# M930.net
KiCad netlist of a schematic drawn in EAGLE
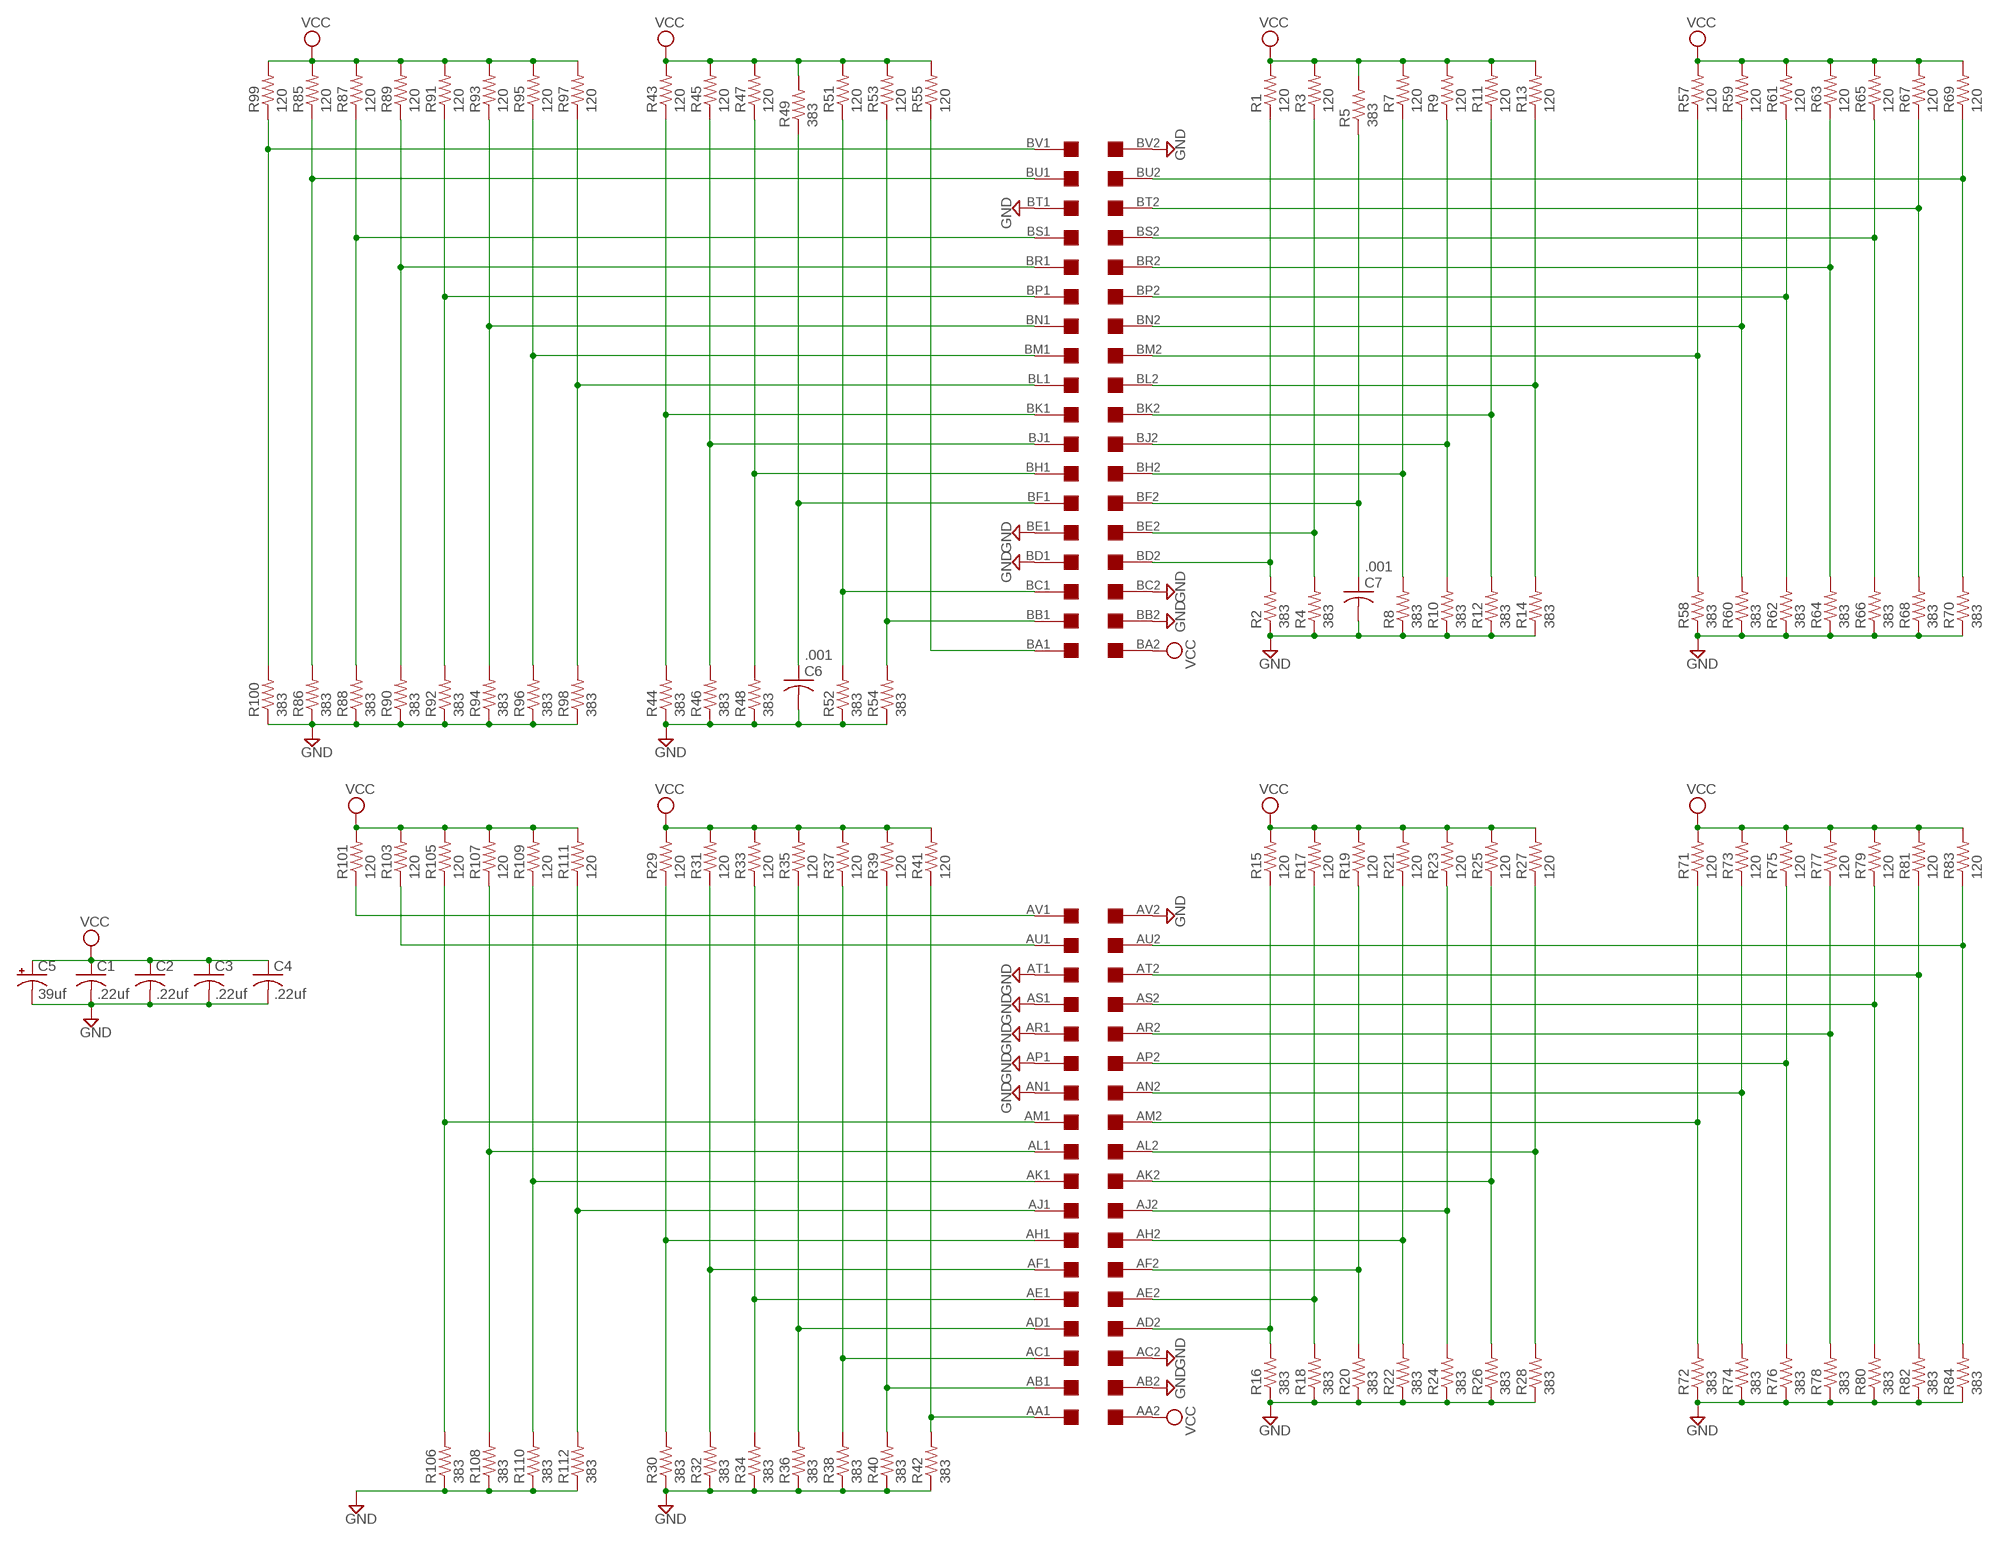
[diagram p0: schematic, sheet 1]

(export (version "E")
  (design (tool "Eeschema 10.0.6"))
  (components
    (comp (ref "C1")
      (value ".22uf")
      (footprint "eagle-import:C050-025X075")
      (libsource (lib "eagle-import") (part "C-US050-025X075"))
    )
    (comp (ref "C2")
      (value ".22uf")
      (footprint "eagle-import:C050-025X075")
      (libsource (lib "eagle-import") (part "C-US050-025X075"))
    )
    (comp (ref "C3")
      (value ".22uf")
      (footprint "eagle-import:C050-025X075")
      (libsource (lib "eagle-import") (part "C-US050-025X075"))
    )
    (comp (ref "C4")
      (value ".22uf")
      (footprint "eagle-import:C050-025X075")
      (libsource (lib "eagle-import") (part "C-US050-025X075"))
    )
    (comp (ref "C5")
      (value "39uf")
      (footprint "eagle-import:E15-5")
      (libsource (lib "eagle-import") (part "CPOL-USE15-5AXIAL"))
    )
    (comp (ref "C6")
      (value ".001")
      (footprint "eagle-import:C050-025X075")
      (libsource (lib "eagle-import") (part "C-US050-025X075"))
    )
    (comp (ref "C7")
      (value ".001")
      (footprint "eagle-import:C050-025X075")
      (libsource (lib "eagle-import") (part "C-US050-025X075"))
    )
    (comp (ref "R1")
      (value "120")
      (footprint "eagle-import:0207_10")
      (libsource (lib "eagle-import") (part "R-US_0207/10"))
    )
    (comp (ref "R2")
      (value "383")
      (footprint "eagle-import:0207_10")
      (libsource (lib "eagle-import") (part "R-US_0207/10"))
    )
    (comp (ref "R3")
      (value "120")
      (footprint "eagle-import:0207_10")
      (libsource (lib "eagle-import") (part "R-US_0207/10"))
    )
    (comp (ref "R4")
      (value "383")
      (footprint "eagle-import:0207_10")
      (libsource (lib "eagle-import") (part "R-US_0207/10"))
    )
    (comp (ref "R5")
      (value "383")
      (footprint "eagle-import:0207_10")
      (libsource (lib "eagle-import") (part "R-US_0207/10"))
    )
    (comp (ref "R7")
      (value "120")
      (footprint "eagle-import:0207_10")
      (libsource (lib "eagle-import") (part "R-US_0207/10"))
    )
    (comp (ref "R8")
      (value "383")
      (footprint "eagle-import:0207_10")
      (libsource (lib "eagle-import") (part "R-US_0207/10"))
    )
    (comp (ref "R9")
      (value "120")
      (footprint "eagle-import:0207_10")
      (libsource (lib "eagle-import") (part "R-US_0207/10"))
    )
    (comp (ref "R10")
      (value "383")
      (footprint "eagle-import:0207_10")
      (libsource (lib "eagle-import") (part "R-US_0207/10"))
    )
    (comp (ref "R11")
      (value "120")
      (footprint "eagle-import:0207_10")
      (libsource (lib "eagle-import") (part "R-US_0207/10"))
    )
    (comp (ref "R12")
      (value "383")
      (footprint "eagle-import:0207_10")
      (libsource (lib "eagle-import") (part "R-US_0207/10"))
    )
    (comp (ref "R13")
      (value "120")
      (footprint "eagle-import:0207_10")
      (libsource (lib "eagle-import") (part "R-US_0207/10"))
    )
    (comp (ref "R14")
      (value "383")
      (footprint "eagle-import:0207_10")
      (libsource (lib "eagle-import") (part "R-US_0207/10"))
    )
    (comp (ref "R15")
      (value "120")
      (footprint "eagle-import:0207_10")
      (libsource (lib "eagle-import") (part "R-US_0207/10"))
    )
    (comp (ref "R16")
      (value "383")
      (footprint "eagle-import:0207_10")
      (libsource (lib "eagle-import") (part "R-US_0207/10"))
    )
    (comp (ref "R17")
      (value "120")
      (footprint "eagle-import:0207_10")
      (libsource (lib "eagle-import") (part "R-US_0207/10"))
    )
    (comp (ref "R18")
      (value "383")
      (footprint "eagle-import:0207_10")
      (libsource (lib "eagle-import") (part "R-US_0207/10"))
    )
    (comp (ref "R19")
      (value "120")
      (footprint "eagle-import:0207_10")
      (libsource (lib "eagle-import") (part "R-US_0207/10"))
    )
    (comp (ref "R20")
      (value "383")
      (footprint "eagle-import:0207_10")
      (libsource (lib "eagle-import") (part "R-US_0207/10"))
    )
    (comp (ref "R21")
      (value "120")
      (footprint "eagle-import:0207_10")
      (libsource (lib "eagle-import") (part "R-US_0207/10"))
    )
    (comp (ref "R22")
      (value "383")
      (footprint "eagle-import:0207_10")
      (libsource (lib "eagle-import") (part "R-US_0207/10"))
    )
    (comp (ref "R23")
      (value "120")
      (footprint "eagle-import:0207_10")
      (libsource (lib "eagle-import") (part "R-US_0207/10"))
    )
    (comp (ref "R24")
      (value "383")
      (footprint "eagle-import:0207_10")
      (libsource (lib "eagle-import") (part "R-US_0207/10"))
    )
    (comp (ref "R25")
      (value "120")
      (footprint "eagle-import:0207_10")
      (libsource (lib "eagle-import") (part "R-US_0207/10"))
    )
    (comp (ref "R26")
      (value "383")
      (footprint "eagle-import:0207_10")
      (libsource (lib "eagle-import") (part "R-US_0207/10"))
    )
    (comp (ref "R27")
      (value "120")
      (footprint "eagle-import:0207_10")
      (libsource (lib "eagle-import") (part "R-US_0207/10"))
    )
    (comp (ref "R28")
      (value "383")
      (footprint "eagle-import:0207_10")
      (libsource (lib "eagle-import") (part "R-US_0207/10"))
    )
    (comp (ref "R29")
      (value "120")
      (footprint "eagle-import:0207_10")
      (libsource (lib "eagle-import") (part "R-US_0207/10"))
    )
    (comp (ref "R30")
      (value "383")
      (footprint "eagle-import:0207_10")
      (libsource (lib "eagle-import") (part "R-US_0207/10"))
    )
    (comp (ref "R31")
      (value "120")
      (footprint "eagle-import:0207_10")
      (libsource (lib "eagle-import") (part "R-US_0207/10"))
    )
    (comp (ref "R32")
      (value "383")
      (footprint "eagle-import:0207_10")
      (libsource (lib "eagle-import") (part "R-US_0207/10"))
    )
    (comp (ref "R33")
      (value "120")
      (footprint "eagle-import:0207_10")
      (libsource (lib "eagle-import") (part "R-US_0207/10"))
    )
    (comp (ref "R34")
      (value "383")
      (footprint "eagle-import:0207_10")
      (libsource (lib "eagle-import") (part "R-US_0207/10"))
    )
    (comp (ref "R35")
      (value "120")
      (footprint "eagle-import:0207_10")
      (libsource (lib "eagle-import") (part "R-US_0207/10"))
    )
    (comp (ref "R36")
      (value "383")
      (footprint "eagle-import:0207_10")
      (libsource (lib "eagle-import") (part "R-US_0207/10"))
    )
    (comp (ref "R37")
      (value "120")
      (footprint "eagle-import:0207_10")
      (libsource (lib "eagle-import") (part "R-US_0207/10"))
    )
    (comp (ref "R38")
      (value "383")
      (footprint "eagle-import:0207_10")
      (libsource (lib "eagle-import") (part "R-US_0207/10"))
    )
    (comp (ref "R39")
      (value "120")
      (footprint "eagle-import:0207_10")
      (libsource (lib "eagle-import") (part "R-US_0207/10"))
    )
    (comp (ref "R40")
      (value "383")
      (footprint "eagle-import:0207_10")
      (libsource (lib "eagle-import") (part "R-US_0207/10"))
    )
    (comp (ref "R41")
      (value "120")
      (footprint "eagle-import:0207_10")
      (libsource (lib "eagle-import") (part "R-US_0207/10"))
    )
    (comp (ref "R42")
      (value "383")
      (footprint "eagle-import:0207_10")
      (libsource (lib "eagle-import") (part "R-US_0207/10"))
    )
    (comp (ref "R43")
      (value "120")
      (footprint "eagle-import:0207_10")
      (libsource (lib "eagle-import") (part "R-US_0207/10"))
    )
    (comp (ref "R44")
      (value "383")
      (footprint "eagle-import:0207_10")
      (libsource (lib "eagle-import") (part "R-US_0207/10"))
    )
    (comp (ref "R45")
      (value "120")
      (footprint "eagle-import:0207_10")
      (libsource (lib "eagle-import") (part "R-US_0207/10"))
    )
    (comp (ref "R46")
      (value "383")
      (footprint "eagle-import:0207_10")
      (libsource (lib "eagle-import") (part "R-US_0207/10"))
    )
    (comp (ref "R47")
      (value "120")
      (footprint "eagle-import:0207_10")
      (libsource (lib "eagle-import") (part "R-US_0207/10"))
    )
    (comp (ref "R48")
      (value "383")
      (footprint "eagle-import:0207_10")
      (libsource (lib "eagle-import") (part "R-US_0207/10"))
    )
    (comp (ref "R49")
      (value "383")
      (footprint "eagle-import:0207_10")
      (libsource (lib "eagle-import") (part "R-US_0207/10"))
    )
    (comp (ref "R51")
      (value "120")
      (footprint "eagle-import:0207_10")
      (libsource (lib "eagle-import") (part "R-US_0207/10"))
    )
    (comp (ref "R52")
      (value "383")
      (footprint "eagle-import:0207_10")
      (libsource (lib "eagle-import") (part "R-US_0207/10"))
    )
    (comp (ref "R53")
      (value "120")
      (footprint "eagle-import:0207_10")
      (libsource (lib "eagle-import") (part "R-US_0207/10"))
    )
    (comp (ref "R54")
      (value "383")
      (footprint "eagle-import:0207_10")
      (libsource (lib "eagle-import") (part "R-US_0207/10"))
    )
    (comp (ref "R55")
      (value "120")
      (footprint "eagle-import:0207_10")
      (libsource (lib "eagle-import") (part "R-US_0207/10"))
    )
    (comp (ref "R57")
      (value "120")
      (footprint "eagle-import:0207_10")
      (libsource (lib "eagle-import") (part "R-US_0207/10"))
    )
    (comp (ref "R58")
      (value "383")
      (footprint "eagle-import:0207_10")
      (libsource (lib "eagle-import") (part "R-US_0207/10"))
    )
    (comp (ref "R59")
      (value "120")
      (footprint "eagle-import:0207_10")
      (libsource (lib "eagle-import") (part "R-US_0207/10"))
    )
    (comp (ref "R60")
      (value "383")
      (footprint "eagle-import:0207_10")
      (libsource (lib "eagle-import") (part "R-US_0207/10"))
    )
    (comp (ref "R61")
      (value "120")
      (footprint "eagle-import:0207_10")
      (libsource (lib "eagle-import") (part "R-US_0207/10"))
    )
    (comp (ref "R62")
      (value "383")
      (footprint "eagle-import:0207_10")
      (libsource (lib "eagle-import") (part "R-US_0207/10"))
    )
    (comp (ref "R63")
      (value "120")
      (footprint "eagle-import:0207_10")
      (libsource (lib "eagle-import") (part "R-US_0207/10"))
    )
    (comp (ref "R64")
      (value "383")
      (footprint "eagle-import:0207_10")
      (libsource (lib "eagle-import") (part "R-US_0207/10"))
    )
    (comp (ref "R65")
      (value "120")
      (footprint "eagle-import:0207_10")
      (libsource (lib "eagle-import") (part "R-US_0207/10"))
    )
    (comp (ref "R66")
      (value "383")
      (footprint "eagle-import:0207_10")
      (libsource (lib "eagle-import") (part "R-US_0207/10"))
    )
    (comp (ref "R67")
      (value "120")
      (footprint "eagle-import:0207_10")
      (libsource (lib "eagle-import") (part "R-US_0207/10"))
    )
    (comp (ref "R68")
      (value "383")
      (footprint "eagle-import:0207_10")
      (libsource (lib "eagle-import") (part "R-US_0207/10"))
    )
    (comp (ref "R69")
      (value "120")
      (footprint "eagle-import:0207_10")
      (libsource (lib "eagle-import") (part "R-US_0207/10"))
    )
    (comp (ref "R70")
      (value "383")
      (footprint "eagle-import:0207_10")
      (libsource (lib "eagle-import") (part "R-US_0207/10"))
    )
    (comp (ref "R71")
      (value "120")
      (footprint "eagle-import:0207_10")
      (libsource (lib "eagle-import") (part "R-US_0207/10"))
    )
    (comp (ref "R72")
      (value "383")
      (footprint "eagle-import:0207_10")
      (libsource (lib "eagle-import") (part "R-US_0207/10"))
    )
    (comp (ref "R73")
      (value "120")
      (footprint "eagle-import:0207_10")
      (libsource (lib "eagle-import") (part "R-US_0207/10"))
    )
    (comp (ref "R74")
      (value "383")
      (footprint "eagle-import:0207_10")
      (libsource (lib "eagle-import") (part "R-US_0207/10"))
    )
    (comp (ref "R75")
      (value "120")
      (footprint "eagle-import:0207_10")
      (libsource (lib "eagle-import") (part "R-US_0207/10"))
    )
    (comp (ref "R76")
      (value "383")
      (footprint "eagle-import:0207_10")
      (libsource (lib "eagle-import") (part "R-US_0207/10"))
    )
    (comp (ref "R77")
      (value "120")
      (footprint "eagle-import:0207_10")
      (libsource (lib "eagle-import") (part "R-US_0207/10"))
    )
    (comp (ref "R78")
      (value "383")
      (footprint "eagle-import:0207_10")
      (libsource (lib "eagle-import") (part "R-US_0207/10"))
    )
    (comp (ref "R79")
      (value "120")
      (footprint "eagle-import:0207_10")
      (libsource (lib "eagle-import") (part "R-US_0207/10"))
    )
    (comp (ref "R80")
      (value "383")
      (footprint "eagle-import:0207_10")
      (libsource (lib "eagle-import") (part "R-US_0207/10"))
    )
    (comp (ref "R81")
      (value "120")
      (footprint "eagle-import:0207_10")
      (libsource (lib "eagle-import") (part "R-US_0207/10"))
    )
    (comp (ref "R82")
      (value "383")
      (footprint "eagle-import:0207_10")
      (libsource (lib "eagle-import") (part "R-US_0207/10"))
    )
    (comp (ref "R83")
      (value "120")
      (footprint "eagle-import:0207_10")
      (libsource (lib "eagle-import") (part "R-US_0207/10"))
    )
    (comp (ref "R84")
      (value "383")
      (footprint "eagle-import:0207_10")
      (libsource (lib "eagle-import") (part "R-US_0207/10"))
    )
    (comp (ref "R85")
      (value "120")
      (footprint "eagle-import:0207_10")
      (libsource (lib "eagle-import") (part "R-US_0207/10"))
    )
    (comp (ref "R86")
      (value "383")
      (footprint "eagle-import:0207_10")
      (libsource (lib "eagle-import") (part "R-US_0207/10"))
    )
    (comp (ref "R87")
      (value "120")
      (footprint "eagle-import:0207_10")
      (libsource (lib "eagle-import") (part "R-US_0207/10"))
    )
    (comp (ref "R88")
      (value "383")
      (footprint "eagle-import:0207_10")
      (libsource (lib "eagle-import") (part "R-US_0207/10"))
    )
    (comp (ref "R89")
      (value "120")
      (footprint "eagle-import:0207_10")
      (libsource (lib "eagle-import") (part "R-US_0207/10"))
    )
    (comp (ref "R90")
      (value "383")
      (footprint "eagle-import:0207_10")
      (libsource (lib "eagle-import") (part "R-US_0207/10"))
    )
    (comp (ref "R91")
      (value "120")
      (footprint "eagle-import:0207_10")
      (libsource (lib "eagle-import") (part "R-US_0207/10"))
    )
    (comp (ref "R92")
      (value "383")
      (footprint "eagle-import:0207_10")
      (libsource (lib "eagle-import") (part "R-US_0207/10"))
    )
    (comp (ref "R93")
      (value "120")
      (footprint "eagle-import:0207_10")
      (libsource (lib "eagle-import") (part "R-US_0207/10"))
    )
    (comp (ref "R94")
      (value "383")
      (footprint "eagle-import:0207_10")
      (libsource (lib "eagle-import") (part "R-US_0207/10"))
    )
    (comp (ref "R95")
      (value "120")
      (footprint "eagle-import:0207_10")
      (libsource (lib "eagle-import") (part "R-US_0207/10"))
    )
    (comp (ref "R96")
      (value "383")
      (footprint "eagle-import:0207_10")
      (libsource (lib "eagle-import") (part "R-US_0207/10"))
    )
    (comp (ref "R97")
      (value "120")
      (footprint "eagle-import:0207_10")
      (libsource (lib "eagle-import") (part "R-US_0207/10"))
    )
    (comp (ref "R98")
      (value "383")
      (footprint "eagle-import:0207_10")
      (libsource (lib "eagle-import") (part "R-US_0207/10"))
    )
    (comp (ref "R99")
      (value "120")
      (footprint "eagle-import:0207_10")
      (libsource (lib "eagle-import") (part "R-US_0207/10"))
    )
    (comp (ref "R100")
      (value "383")
      (footprint "eagle-import:0207_10")
      (libsource (lib "eagle-import") (part "R-US_0207/10"))
    )
    (comp (ref "R101")
      (value "120")
      (footprint "eagle-import:0207_10")
      (libsource (lib "eagle-import") (part "R-US_0207/10"))
    )
    (comp (ref "R103")
      (value "120")
      (footprint "eagle-import:0207_10")
      (libsource (lib "eagle-import") (part "R-US_0207/10"))
    )
    (comp (ref "R105")
      (value "120")
      (footprint "eagle-import:0207_10")
      (libsource (lib "eagle-import") (part "R-US_0207/10"))
    )
    (comp (ref "R106")
      (value "383")
      (footprint "eagle-import:0207_10")
      (libsource (lib "eagle-import") (part "R-US_0207/10"))
    )
    (comp (ref "R107")
      (value "120")
      (footprint "eagle-import:0207_10")
      (libsource (lib "eagle-import") (part "R-US_0207/10"))
    )
    (comp (ref "R108")
      (value "383")
      (footprint "eagle-import:0207_10")
      (libsource (lib "eagle-import") (part "R-US_0207/10"))
    )
    (comp (ref "R109")
      (value "120")
      (footprint "eagle-import:0207_10")
      (libsource (lib "eagle-import") (part "R-US_0207/10"))
    )
    (comp (ref "R110")
      (value "383")
      (footprint "eagle-import:0207_10")
      (libsource (lib "eagle-import") (part "R-US_0207/10"))
    )
    (comp (ref "R111")
      (value "120")
      (footprint "eagle-import:0207_10")
      (libsource (lib "eagle-import") (part "R-US_0207/10"))
    )
    (comp (ref "R112")
      (value "383")
      (footprint "eagle-import:0207_10")
      (libsource (lib "eagle-import") (part "R-US_0207/10"))
    )
    (comp (ref "U$1")
      (value "DOUBLE")
      (footprint "eagle-import:EDGE-CON4")
      (libsource (lib "eagle-import") (part "DOUBLE"))
    )
  )
  (nets
    (net (code "1") (name "GND") (class "Default")
      (node (ref "C1") (pin "2") (pinfunction "2_2") (pintype "passive"))
      (node (ref "C2") (pin "2") (pinfunction "2_2") (pintype "passive"))
      (node (ref "C3") (pin "2") (pinfunction "2_2") (pintype "passive"))
      (node (ref "C4") (pin "2") (pinfunction "2_2") (pintype "passive"))
      (node (ref "C5") (pin "-") (pinfunction "-_-") (pintype "passive"))
      (node (ref "C6") (pin "2") (pinfunction "2_2") (pintype "passive"))
      (node (ref "C7") (pin "2") (pinfunction "2_2") (pintype "passive"))
      (node (ref "R10") (pin "1") (pinfunction "1_1") (pintype "passive"))
      (node (ref "R100") (pin "1") (pinfunction "1_1") (pintype "passive"))
      (node (ref "R106") (pin "1") (pinfunction "1_1") (pintype "passive"))
      (node (ref "R108") (pin "1") (pinfunction "1_1") (pintype "passive"))
      (node (ref "R110") (pin "1") (pinfunction "1_1") (pintype "passive"))
      (node (ref "R112") (pin "1") (pinfunction "1_1") (pintype "passive"))
      (node (ref "R12") (pin "1") (pinfunction "1_1") (pintype "passive"))
      (node (ref "R14") (pin "1") (pinfunction "1_1") (pintype "passive"))
      (node (ref "R16") (pin "1") (pinfunction "1_1") (pintype "passive"))
      (node (ref "R18") (pin "1") (pinfunction "1_1") (pintype "passive"))
      (node (ref "R2") (pin "1") (pinfunction "1_1") (pintype "passive"))
      (node (ref "R20") (pin "1") (pinfunction "1_1") (pintype "passive"))
      (node (ref "R22") (pin "1") (pinfunction "1_1") (pintype "passive"))
      (node (ref "R24") (pin "1") (pinfunction "1_1") (pintype "passive"))
      (node (ref "R26") (pin "1") (pinfunction "1_1") (pintype "passive"))
      (node (ref "R28") (pin "1") (pinfunction "1_1") (pintype "passive"))
      (node (ref "R30") (pin "1") (pinfunction "1_1") (pintype "passive"))
      (node (ref "R32") (pin "1") (pinfunction "1_1") (pintype "passive"))
      (node (ref "R34") (pin "1") (pinfunction "1_1") (pintype "passive"))
      (node (ref "R36") (pin "1") (pinfunction "1_1") (pintype "passive"))
      (node (ref "R38") (pin "1") (pinfunction "1_1") (pintype "passive"))
      (node (ref "R4") (pin "1") (pinfunction "1_1") (pintype "passive"))
      (node (ref "R40") (pin "1") (pinfunction "1_1") (pintype "passive"))
      (node (ref "R42") (pin "1") (pinfunction "1_1") (pintype "passive"))
      (node (ref "R44") (pin "1") (pinfunction "1_1") (pintype "passive"))
      (node (ref "R46") (pin "1") (pinfunction "1_1") (pintype "passive"))
      (node (ref "R48") (pin "1") (pinfunction "1_1") (pintype "passive"))
      (node (ref "R52") (pin "1") (pinfunction "1_1") (pintype "passive"))
      (node (ref "R54") (pin "1") (pinfunction "1_1") (pintype "passive"))
      (node (ref "R58") (pin "1") (pinfunction "1_1") (pintype "passive"))
      (node (ref "R60") (pin "1") (pinfunction "1_1") (pintype "passive"))
      (node (ref "R62") (pin "1") (pinfunction "1_1") (pintype "passive"))
      (node (ref "R64") (pin "1") (pinfunction "1_1") (pintype "passive"))
      (node (ref "R66") (pin "1") (pinfunction "1_1") (pintype "passive"))
      (node (ref "R68") (pin "1") (pinfunction "1_1") (pintype "passive"))
      (node (ref "R70") (pin "1") (pinfunction "1_1") (pintype "passive"))
      (node (ref "R72") (pin "1") (pinfunction "1_1") (pintype "passive"))
      (node (ref "R74") (pin "1") (pinfunction "1_1") (pintype "passive"))
      (node (ref "R76") (pin "1") (pinfunction "1_1") (pintype "passive"))
      (node (ref "R78") (pin "1") (pinfunction "1_1") (pintype "passive"))
      (node (ref "R8") (pin "1") (pinfunction "1_1") (pintype "passive"))
      (node (ref "R80") (pin "1") (pinfunction "1_1") (pintype "passive"))
      (node (ref "R82") (pin "1") (pinfunction "1_1") (pintype "passive"))
      (node (ref "R84") (pin "1") (pinfunction "1_1") (pintype "passive"))
      (node (ref "R86") (pin "1") (pinfunction "1_1") (pintype "passive"))
      (node (ref "R88") (pin "1") (pinfunction "1_1") (pintype "passive"))
      (node (ref "R90") (pin "1") (pinfunction "1_1") (pintype "passive"))
      (node (ref "R92") (pin "1") (pinfunction "1_1") (pintype "passive"))
      (node (ref "R94") (pin "1") (pinfunction "1_1") (pintype "passive"))
      (node (ref "R96") (pin "1") (pinfunction "1_1") (pintype "passive"))
      (node (ref "R98") (pin "1") (pinfunction "1_1") (pintype "passive"))
      (node (ref "U$1") (pin "AB2") (pinfunction "1_AB2") (pintype "bidirectional"))
      (node (ref "U$1") (pin "AC2") (pinfunction "1_AC2") (pintype "bidirectional"))
      (node (ref "U$1") (pin "AN1") (pinfunction "1_AN1") (pintype "bidirectional"))
      (node (ref "U$1") (pin "AP1") (pinfunction "1_AP1") (pintype "bidirectional"))
      (node (ref "U$1") (pin "AR1") (pinfunction "1_AR1") (pintype "bidirectional"))
      (node (ref "U$1") (pin "AS1") (pinfunction "1_AS1") (pintype "bidirectional"))
      (node (ref "U$1") (pin "AT1") (pinfunction "1_AT1") (pintype "bidirectional"))
      (node (ref "U$1") (pin "AV2") (pinfunction "1_AV2") (pintype "bidirectional"))
      (node (ref "U$1") (pin "BB2") (pinfunction "1_BB2") (pintype "bidirectional"))
      (node (ref "U$1") (pin "BC2") (pinfunction "1_BC2") (pintype "bidirectional"))
      (node (ref "U$1") (pin "BD1") (pinfunction "1_BD1") (pintype "bidirectional"))
      (node (ref "U$1") (pin "BE1") (pinfunction "1_BE1") (pintype "bidirectional"))
      (node (ref "U$1") (pin "BT1") (pinfunction "1_BT1") (pintype "bidirectional"))
      (node (ref "U$1") (pin "BV2") (pinfunction "1_BV2") (pintype "bidirectional"))
    )
    (net (code "2") (name "Net-(U$1A-1)") (class "Default")
      (node (ref "R41") (pin "1") (pinfunction "1_1") (pintype "passive"))
      (node (ref "R42") (pin "2") (pinfunction "2_2") (pintype "passive"))
      (node (ref "U$1") (pin "AA1") (pinfunction "1_AA1") (pintype "bidirectional"))
    )
    (net (code "3") (name "Net-(U$1AB-1)") (class "Default")
      (node (ref "R77") (pin "1") (pinfunction "1_1") (pintype "passive"))
      (node (ref "R78") (pin "2") (pinfunction "2_2") (pintype "passive"))
      (node (ref "U$1") (pin "AR2") (pinfunction "1_AR2") (pintype "bidirectional"))
    )
    (net (code "4") (name "Net-(U$1AD-1)") (class "Default")
      (node (ref "R79") (pin "1") (pinfunction "1_1") (pintype "passive"))
      (node (ref "R80") (pin "2") (pinfunction "2_2") (pintype "passive"))
      (node (ref "U$1") (pin "AS2") (pinfunction "1_AS2") (pintype "bidirectional"))
    )
    (net (code "5") (name "Net-(U$1AF-1)") (class "Default")
      (node (ref "R81") (pin "1") (pinfunction "1_1") (pintype "passive"))
      (node (ref "R82") (pin "2") (pinfunction "2_2") (pintype "passive"))
      (node (ref "U$1") (pin "AT2") (pinfunction "1_AT2") (pintype "bidirectional"))
    )
    (net (code "6") (name "Net-(U$1AG-1)") (class "Default")
      (node (ref "R103") (pin "1") (pinfunction "1_1") (pintype "passive"))
      (node (ref "U$1") (pin "AU1") (pinfunction "1_AU1") (pintype "bidirectional"))
    )
    (net (code "7") (name "Net-(U$1AH-1)") (class "Default")
      (node (ref "R83") (pin "1") (pinfunction "1_1") (pintype "passive"))
      (node (ref "R84") (pin "2") (pinfunction "2_2") (pintype "passive"))
      (node (ref "U$1") (pin "AU2") (pinfunction "1_AU2") (pintype "bidirectional"))
    )
    (net (code "8") (name "Net-(U$1AI-1)") (class "Default")
      (node (ref "R101") (pin "1") (pinfunction "1_1") (pintype "passive"))
      (node (ref "U$1") (pin "AV1") (pinfunction "1_AV1") (pintype "bidirectional"))
    )
    (net (code "9") (name "Net-(U$1AK-1)") (class "Default")
      (node (ref "R55") (pin "1") (pinfunction "1_1") (pintype "passive"))
      (node (ref "U$1") (pin "BA1") (pinfunction "1_BA1") (pintype "bidirectional"))
    )
    (net (code "10") (name "Net-(U$1AM-1)") (class "Default")
      (node (ref "R53") (pin "1") (pinfunction "1_1") (pintype "passive"))
      (node (ref "R54") (pin "2") (pinfunction "2_2") (pintype "passive"))
      (node (ref "U$1") (pin "BB1") (pinfunction "1_BB1") (pintype "bidirectional"))
    )
    (net (code "11") (name "Net-(U$1AO-1)") (class "Default")
      (node (ref "R51") (pin "1") (pinfunction "1_1") (pintype "passive"))
      (node (ref "R52") (pin "2") (pinfunction "2_2") (pintype "passive"))
      (node (ref "U$1") (pin "BC1") (pinfunction "1_BC1") (pintype "bidirectional"))
    )
    (net (code "12") (name "Net-(U$1AR-1)") (class "Default")
      (node (ref "R1") (pin "1") (pinfunction "1_1") (pintype "passive"))
      (node (ref "R2") (pin "2") (pinfunction "2_2") (pintype "passive"))
      (node (ref "U$1") (pin "BD2") (pinfunction "1_BD2") (pintype "bidirectional"))
    )
    (net (code "13") (name "Net-(U$1AT-1)") (class "Default")
      (node (ref "R3") (pin "1") (pinfunction "1_1") (pintype "passive"))
      (node (ref "R4") (pin "2") (pinfunction "2_2") (pintype "passive"))
      (node (ref "U$1") (pin "BE2") (pinfunction "1_BE2") (pintype "bidirectional"))
    )
    (net (code "14") (name "Net-(U$1AU-1)") (class "Default")
      (node (ref "C6") (pin "1") (pinfunction "1_1") (pintype "passive"))
      (node (ref "R49") (pin "1") (pinfunction "1_1") (pintype "passive"))
      (node (ref "U$1") (pin "BF1") (pinfunction "1_BF1") (pintype "bidirectional"))
    )
    (net (code "15") (name "Net-(U$1AV-1)") (class "Default")
      (node (ref "C7") (pin "1") (pinfunction "1_1") (pintype "passive"))
      (node (ref "R5") (pin "1") (pinfunction "1_1") (pintype "passive"))
      (node (ref "U$1") (pin "BF2") (pinfunction "1_BF2") (pintype "bidirectional"))
    )
    (net (code "16") (name "Net-(U$1AW-1)") (class "Default")
      (node (ref "R47") (pin "1") (pinfunction "1_1") (pintype "passive"))
      (node (ref "R48") (pin "2") (pinfunction "2_2") (pintype "passive"))
      (node (ref "U$1") (pin "BH1") (pinfunction "1_BH1") (pintype "bidirectional"))
    )
    (net (code "17") (name "Net-(U$1AX-1)") (class "Default")
      (node (ref "R7") (pin "1") (pinfunction "1_1") (pintype "passive"))
      (node (ref "R8") (pin "2") (pinfunction "2_2") (pintype "passive"))
      (node (ref "U$1") (pin "BH2") (pinfunction "1_BH2") (pintype "bidirectional"))
    )
    (net (code "18") (name "Net-(U$1AY-1)") (class "Default")
      (node (ref "R45") (pin "1") (pinfunction "1_1") (pintype "passive"))
      (node (ref "R46") (pin "2") (pinfunction "2_2") (pintype "passive"))
      (node (ref "U$1") (pin "BJ1") (pinfunction "1_BJ1") (pintype "bidirectional"))
    )
    (net (code "19") (name "Net-(U$1AZ-1)") (class "Default")
      (node (ref "R10") (pin "2") (pinfunction "2_2") (pintype "passive"))
      (node (ref "R9") (pin "1") (pinfunction "1_1") (pintype "passive"))
      (node (ref "U$1") (pin "BJ2") (pinfunction "1_BJ2") (pintype "bidirectional"))
    )
    (net (code "20") (name "Net-(U$1BA-1)") (class "Default")
      (node (ref "R43") (pin "1") (pinfunction "1_1") (pintype "passive"))
      (node (ref "R44") (pin "2") (pinfunction "2_2") (pintype "passive"))
      (node (ref "U$1") (pin "BK1") (pinfunction "1_BK1") (pintype "bidirectional"))
    )
    (net (code "21") (name "Net-(U$1BB-1)") (class "Default")
      (node (ref "R11") (pin "1") (pinfunction "1_1") (pintype "passive"))
      (node (ref "R12") (pin "2") (pinfunction "2_2") (pintype "passive"))
      (node (ref "U$1") (pin "BK2") (pinfunction "1_BK2") (pintype "bidirectional"))
    )
    (net (code "22") (name "Net-(U$1BC-1)") (class "Default")
      (node (ref "R97") (pin "1") (pinfunction "1_1") (pintype "passive"))
      (node (ref "R98") (pin "2") (pinfunction "2_2") (pintype "passive"))
      (node (ref "U$1") (pin "BL1") (pinfunction "1_BL1") (pintype "bidirectional"))
    )
    (net (code "23") (name "Net-(U$1BD-1)") (class "Default")
      (node (ref "R13") (pin "1") (pinfunction "1_1") (pintype "passive"))
      (node (ref "R14") (pin "2") (pinfunction "2_2") (pintype "passive"))
      (node (ref "U$1") (pin "BL2") (pinfunction "1_BL2") (pintype "bidirectional"))
    )
    (net (code "24") (name "Net-(U$1BE-1)") (class "Default")
      (node (ref "R95") (pin "1") (pinfunction "1_1") (pintype "passive"))
      (node (ref "R96") (pin "2") (pinfunction "2_2") (pintype "passive"))
      (node (ref "U$1") (pin "BM1") (pinfunction "1_BM1") (pintype "bidirectional"))
    )
    (net (code "25") (name "Net-(U$1BF-1)") (class "Default")
      (node (ref "R57") (pin "1") (pinfunction "1_1") (pintype "passive"))
      (node (ref "R58") (pin "2") (pinfunction "2_2") (pintype "passive"))
      (node (ref "U$1") (pin "BM2") (pinfunction "1_BM2") (pintype "bidirectional"))
    )
    (net (code "26") (name "Net-(U$1BG-1)") (class "Default")
      (node (ref "R93") (pin "1") (pinfunction "1_1") (pintype "passive"))
      (node (ref "R94") (pin "2") (pinfunction "2_2") (pintype "passive"))
      (node (ref "U$1") (pin "BN1") (pinfunction "1_BN1") (pintype "bidirectional"))
    )
    (net (code "27") (name "Net-(U$1BH-1)") (class "Default")
      (node (ref "R59") (pin "1") (pinfunction "1_1") (pintype "passive"))
      (node (ref "R60") (pin "2") (pinfunction "2_2") (pintype "passive"))
      (node (ref "U$1") (pin "BN2") (pinfunction "1_BN2") (pintype "bidirectional"))
    )
    (net (code "28") (name "Net-(U$1BI-1)") (class "Default")
      (node (ref "R91") (pin "1") (pinfunction "1_1") (pintype "passive"))
      (node (ref "R92") (pin "2") (pinfunction "2_2") (pintype "passive"))
      (node (ref "U$1") (pin "BP1") (pinfunction "1_BP1") (pintype "bidirectional"))
    )
    (net (code "29") (name "Net-(U$1BJ-1)") (class "Default")
      (node (ref "R61") (pin "1") (pinfunction "1_1") (pintype "passive"))
      (node (ref "R62") (pin "2") (pinfunction "2_2") (pintype "passive"))
      (node (ref "U$1") (pin "BP2") (pinfunction "1_BP2") (pintype "bidirectional"))
    )
    (net (code "30") (name "Net-(U$1BK-1)") (class "Default")
      (node (ref "R89") (pin "1") (pinfunction "1_1") (pintype "passive"))
      (node (ref "R90") (pin "2") (pinfunction "2_2") (pintype "passive"))
      (node (ref "U$1") (pin "BR1") (pinfunction "1_BR1") (pintype "bidirectional"))
    )
    (net (code "31") (name "Net-(U$1BL-1)") (class "Default")
      (node (ref "R63") (pin "1") (pinfunction "1_1") (pintype "passive"))
      (node (ref "R64") (pin "2") (pinfunction "2_2") (pintype "passive"))
      (node (ref "U$1") (pin "BR2") (pinfunction "1_BR2") (pintype "bidirectional"))
    )
    (net (code "32") (name "Net-(U$1BM-1)") (class "Default")
      (node (ref "R87") (pin "1") (pinfunction "1_1") (pintype "passive"))
      (node (ref "R88") (pin "2") (pinfunction "2_2") (pintype "passive"))
      (node (ref "U$1") (pin "BS1") (pinfunction "1_BS1") (pintype "bidirectional"))
    )
    (net (code "33") (name "Net-(U$1BN-1)") (class "Default")
      (node (ref "R65") (pin "1") (pinfunction "1_1") (pintype "passive"))
      (node (ref "R66") (pin "2") (pinfunction "2_2") (pintype "passive"))
      (node (ref "U$1") (pin "BS2") (pinfunction "1_BS2") (pintype "bidirectional"))
    )
    (net (code "34") (name "Net-(U$1BP-1)") (class "Default")
      (node (ref "R67") (pin "1") (pinfunction "1_1") (pintype "passive"))
      (node (ref "R68") (pin "2") (pinfunction "2_2") (pintype "passive"))
      (node (ref "U$1") (pin "BT2") (pinfunction "1_BT2") (pintype "bidirectional"))
    )
    (net (code "35") (name "Net-(U$1BQ-1)") (class "Default")
      (node (ref "R85") (pin "1") (pinfunction "1_1") (pintype "passive"))
      (node (ref "R86") (pin "2") (pinfunction "2_2") (pintype "passive"))
      (node (ref "U$1") (pin "BU1") (pinfunction "1_BU1") (pintype "bidirectional"))
    )
    (net (code "36") (name "Net-(U$1BR-1)") (class "Default")
      (node (ref "R69") (pin "1") (pinfunction "1_1") (pintype "passive"))
      (node (ref "R70") (pin "2") (pinfunction "2_2") (pintype "passive"))
      (node (ref "U$1") (pin "BU2") (pinfunction "1_BU2") (pintype "bidirectional"))
    )
    (net (code "37") (name "Net-(U$1BS-1)") (class "Default")
      (node (ref "R100") (pin "2") (pinfunction "2_2") (pintype "passive"))
      (node (ref "R99") (pin "1") (pinfunction "1_1") (pintype "passive"))
      (node (ref "U$1") (pin "BV1") (pinfunction "1_BV1") (pintype "bidirectional"))
    )
    (net (code "38") (name "Net-(U$1C-1)") (class "Default")
      (node (ref "R39") (pin "1") (pinfunction "1_1") (pintype "passive"))
      (node (ref "R40") (pin "2") (pinfunction "2_2") (pintype "passive"))
      (node (ref "U$1") (pin "AB1") (pinfunction "1_AB1") (pintype "bidirectional"))
    )
    (net (code "39") (name "Net-(U$1E-1)") (class "Default")
      (node (ref "R37") (pin "1") (pinfunction "1_1") (pintype "passive"))
      (node (ref "R38") (pin "2") (pinfunction "2_2") (pintype "passive"))
      (node (ref "U$1") (pin "AC1") (pinfunction "1_AC1") (pintype "bidirectional"))
    )
    (net (code "40") (name "Net-(U$1G-1)") (class "Default")
      (node (ref "R35") (pin "1") (pinfunction "1_1") (pintype "passive"))
      (node (ref "R36") (pin "2") (pinfunction "2_2") (pintype "passive"))
      (node (ref "U$1") (pin "AD1") (pinfunction "1_AD1") (pintype "bidirectional"))
    )
    (net (code "41") (name "Net-(U$1H-1)") (class "Default")
      (node (ref "R15") (pin "1") (pinfunction "1_1") (pintype "passive"))
      (node (ref "R16") (pin "2") (pinfunction "2_2") (pintype "passive"))
      (node (ref "U$1") (pin "AD2") (pinfunction "1_AD2") (pintype "bidirectional"))
    )
    (net (code "42") (name "Net-(U$1I-1)") (class "Default")
      (node (ref "R33") (pin "1") (pinfunction "1_1") (pintype "passive"))
      (node (ref "R34") (pin "2") (pinfunction "2_2") (pintype "passive"))
      (node (ref "U$1") (pin "AE1") (pinfunction "1_AE1") (pintype "bidirectional"))
    )
    (net (code "43") (name "Net-(U$1J-1)") (class "Default")
      (node (ref "R17") (pin "1") (pinfunction "1_1") (pintype "passive"))
      (node (ref "R18") (pin "2") (pinfunction "2_2") (pintype "passive"))
      (node (ref "U$1") (pin "AE2") (pinfunction "1_AE2") (pintype "bidirectional"))
    )
    (net (code "44") (name "Net-(U$1K-1)") (class "Default")
      (node (ref "R31") (pin "1") (pinfunction "1_1") (pintype "passive"))
      (node (ref "R32") (pin "2") (pinfunction "2_2") (pintype "passive"))
      (node (ref "U$1") (pin "AF1") (pinfunction "1_AF1") (pintype "bidirectional"))
    )
    (net (code "45") (name "Net-(U$1L-1)") (class "Default")
      (node (ref "R19") (pin "1") (pinfunction "1_1") (pintype "passive"))
      (node (ref "R20") (pin "2") (pinfunction "2_2") (pintype "passive"))
      (node (ref "U$1") (pin "AF2") (pinfunction "1_AF2") (pintype "bidirectional"))
    )
    (net (code "46") (name "Net-(U$1M-1)") (class "Default")
      (node (ref "R29") (pin "1") (pinfunction "1_1") (pintype "passive"))
      (node (ref "R30") (pin "2") (pinfunction "2_2") (pintype "passive"))
      (node (ref "U$1") (pin "AH1") (pinfunction "1_AH1") (pintype "bidirectional"))
    )
    (net (code "47") (name "Net-(U$1N-1)") (class "Default")
      (node (ref "R21") (pin "1") (pinfunction "1_1") (pintype "passive"))
      (node (ref "R22") (pin "2") (pinfunction "2_2") (pintype "passive"))
      (node (ref "U$1") (pin "AH2") (pinfunction "1_AH2") (pintype "bidirectional"))
    )
    (net (code "48") (name "Net-(U$1O-1)") (class "Default")
      (node (ref "R111") (pin "1") (pinfunction "1_1") (pintype "passive"))
      (node (ref "R112") (pin "2") (pinfunction "2_2") (pintype "passive"))
      (node (ref "U$1") (pin "AJ1") (pinfunction "1_AJ1") (pintype "bidirectional"))
    )
    (net (code "49") (name "Net-(U$1P-1)") (class "Default")
      (node (ref "R23") (pin "1") (pinfunction "1_1") (pintype "passive"))
      (node (ref "R24") (pin "2") (pinfunction "2_2") (pintype "passive"))
      (node (ref "U$1") (pin "AJ2") (pinfunction "1_AJ2") (pintype "bidirectional"))
    )
    (net (code "50") (name "Net-(U$1Q-1)") (class "Default")
      (node (ref "R109") (pin "1") (pinfunction "1_1") (pintype "passive"))
      (node (ref "R110") (pin "2") (pinfunction "2_2") (pintype "passive"))
      (node (ref "U$1") (pin "AK1") (pinfunction "1_AK1") (pintype "bidirectional"))
    )
    (net (code "51") (name "Net-(U$1R-1)") (class "Default")
      (node (ref "R25") (pin "1") (pinfunction "1_1") (pintype "passive"))
      (node (ref "R26") (pin "2") (pinfunction "2_2") (pintype "passive"))
      (node (ref "U$1") (pin "AK2") (pinfunction "1_AK2") (pintype "bidirectional"))
    )
    (net (code "52") (name "Net-(U$1S-1)") (class "Default")
      (node (ref "R107") (pin "1") (pinfunction "1_1") (pintype "passive"))
      (node (ref "R108") (pin "2") (pinfunction "2_2") (pintype "passive"))
      (node (ref "U$1") (pin "AL1") (pinfunction "1_AL1") (pintype "bidirectional"))
    )
    (net (code "53") (name "Net-(U$1T-1)") (class "Default")
      (node (ref "R27") (pin "1") (pinfunction "1_1") (pintype "passive"))
      (node (ref "R28") (pin "2") (pinfunction "2_2") (pintype "passive"))
      (node (ref "U$1") (pin "AL2") (pinfunction "1_AL2") (pintype "bidirectional"))
    )
    (net (code "54") (name "Net-(U$1U-1)") (class "Default")
      (node (ref "R105") (pin "1") (pinfunction "1_1") (pintype "passive"))
      (node (ref "R106") (pin "2") (pinfunction "2_2") (pintype "passive"))
      (node (ref "U$1") (pin "AM1") (pinfunction "1_AM1") (pintype "bidirectional"))
    )
    (net (code "55") (name "Net-(U$1V-1)") (class "Default")
      (node (ref "R71") (pin "1") (pinfunction "1_1") (pintype "passive"))
      (node (ref "R72") (pin "2") (pinfunction "2_2") (pintype "passive"))
      (node (ref "U$1") (pin "AM2") (pinfunction "1_AM2") (pintype "bidirectional"))
    )
    (net (code "56") (name "Net-(U$1X-1)") (class "Default")
      (node (ref "R73") (pin "1") (pinfunction "1_1") (pintype "passive"))
      (node (ref "R74") (pin "2") (pinfunction "2_2") (pintype "passive"))
      (node (ref "U$1") (pin "AN2") (pinfunction "1_AN2") (pintype "bidirectional"))
    )
    (net (code "57") (name "Net-(U$1Z-1)") (class "Default")
      (node (ref "R75") (pin "1") (pinfunction "1_1") (pintype "passive"))
      (node (ref "R76") (pin "2") (pinfunction "2_2") (pintype "passive"))
      (node (ref "U$1") (pin "AP2") (pinfunction "1_AP2") (pintype "bidirectional"))
    )
    (net (code "58") (name "VCC") (class "Default")
      (node (ref "C1") (pin "1") (pinfunction "1_1") (pintype "passive"))
      (node (ref "C2") (pin "1") (pinfunction "1_1") (pintype "passive"))
      (node (ref "C3") (pin "1") (pinfunction "1_1") (pintype "passive"))
      (node (ref "C4") (pin "1") (pinfunction "1_1") (pintype "passive"))
      (node (ref "C5") (pin "+") (pinfunction "+_+") (pintype "passive"))
      (node (ref "R1") (pin "2") (pinfunction "2_2") (pintype "passive"))
      (node (ref "R101") (pin "2") (pinfunction "2_2") (pintype "passive"))
      (node (ref "R103") (pin "2") (pinfunction "2_2") (pintype "passive"))
      (node (ref "R105") (pin "2") (pinfunction "2_2") (pintype "passive"))
      (node (ref "R107") (pin "2") (pinfunction "2_2") (pintype "passive"))
      (node (ref "R109") (pin "2") (pinfunction "2_2") (pintype "passive"))
      (node (ref "R11") (pin "2") (pinfunction "2_2") (pintype "passive"))
      (node (ref "R111") (pin "2") (pinfunction "2_2") (pintype "passive"))
      (node (ref "R13") (pin "2") (pinfunction "2_2") (pintype "passive"))
      (node (ref "R15") (pin "2") (pinfunction "2_2") (pintype "passive"))
      (node (ref "R17") (pin "2") (pinfunction "2_2") (pintype "passive"))
      (node (ref "R19") (pin "2") (pinfunction "2_2") (pintype "passive"))
      (node (ref "R21") (pin "2") (pinfunction "2_2") (pintype "passive"))
      (node (ref "R23") (pin "2") (pinfunction "2_2") (pintype "passive"))
      (node (ref "R25") (pin "2") (pinfunction "2_2") (pintype "passive"))
      (node (ref "R27") (pin "2") (pinfunction "2_2") (pintype "passive"))
      (node (ref "R29") (pin "2") (pinfunction "2_2") (pintype "passive"))
      (node (ref "R3") (pin "2") (pinfunction "2_2") (pintype "passive"))
      (node (ref "R31") (pin "2") (pinfunction "2_2") (pintype "passive"))
      (node (ref "R33") (pin "2") (pinfunction "2_2") (pintype "passive"))
      (node (ref "R35") (pin "2") (pinfunction "2_2") (pintype "passive"))
      (node (ref "R37") (pin "2") (pinfunction "2_2") (pintype "passive"))
      (node (ref "R39") (pin "2") (pinfunction "2_2") (pintype "passive"))
      (node (ref "R41") (pin "2") (pinfunction "2_2") (pintype "passive"))
      (node (ref "R43") (pin "2") (pinfunction "2_2") (pintype "passive"))
      (node (ref "R45") (pin "2") (pinfunction "2_2") (pintype "passive"))
      (node (ref "R47") (pin "2") (pinfunction "2_2") (pintype "passive"))
      (node (ref "R49") (pin "2") (pinfunction "2_2") (pintype "passive"))
      (node (ref "R5") (pin "2") (pinfunction "2_2") (pintype "passive"))
      (node (ref "R51") (pin "2") (pinfunction "2_2") (pintype "passive"))
      (node (ref "R53") (pin "2") (pinfunction "2_2") (pintype "passive"))
      (node (ref "R55") (pin "2") (pinfunction "2_2") (pintype "passive"))
      (node (ref "R57") (pin "2") (pinfunction "2_2") (pintype "passive"))
      (node (ref "R59") (pin "2") (pinfunction "2_2") (pintype "passive"))
      (node (ref "R61") (pin "2") (pinfunction "2_2") (pintype "passive"))
      (node (ref "R63") (pin "2") (pinfunction "2_2") (pintype "passive"))
      (node (ref "R65") (pin "2") (pinfunction "2_2") (pintype "passive"))
      (node (ref "R67") (pin "2") (pinfunction "2_2") (pintype "passive"))
      (node (ref "R69") (pin "2") (pinfunction "2_2") (pintype "passive"))
      (node (ref "R7") (pin "2") (pinfunction "2_2") (pintype "passive"))
      (node (ref "R71") (pin "2") (pinfunction "2_2") (pintype "passive"))
      (node (ref "R73") (pin "2") (pinfunction "2_2") (pintype "passive"))
      (node (ref "R75") (pin "2") (pinfunction "2_2") (pintype "passive"))
      (node (ref "R77") (pin "2") (pinfunction "2_2") (pintype "passive"))
      (node (ref "R79") (pin "2") (pinfunction "2_2") (pintype "passive"))
      (node (ref "R81") (pin "2") (pinfunction "2_2") (pintype "passive"))
      (node (ref "R83") (pin "2") (pinfunction "2_2") (pintype "passive"))
      (node (ref "R85") (pin "2") (pinfunction "2_2") (pintype "passive"))
      (node (ref "R87") (pin "2") (pinfunction "2_2") (pintype "passive"))
      (node (ref "R89") (pin "2") (pinfunction "2_2") (pintype "passive"))
      (node (ref "R9") (pin "2") (pinfunction "2_2") (pintype "passive"))
      (node (ref "R91") (pin "2") (pinfunction "2_2") (pintype "passive"))
      (node (ref "R93") (pin "2") (pinfunction "2_2") (pintype "passive"))
      (node (ref "R95") (pin "2") (pinfunction "2_2") (pintype "passive"))
      (node (ref "R97") (pin "2") (pinfunction "2_2") (pintype "passive"))
      (node (ref "R99") (pin "2") (pinfunction "2_2") (pintype "passive"))
      (node (ref "U$1") (pin "AA2") (pinfunction "1_AA2") (pintype "bidirectional"))
      (node (ref "U$1") (pin "BA2") (pinfunction "1_BA2") (pintype "bidirectional"))
    )
  )
)
